# Ad_-_ESP-12F.net
KiCad netlist of a schematic drawn in Altium Designer
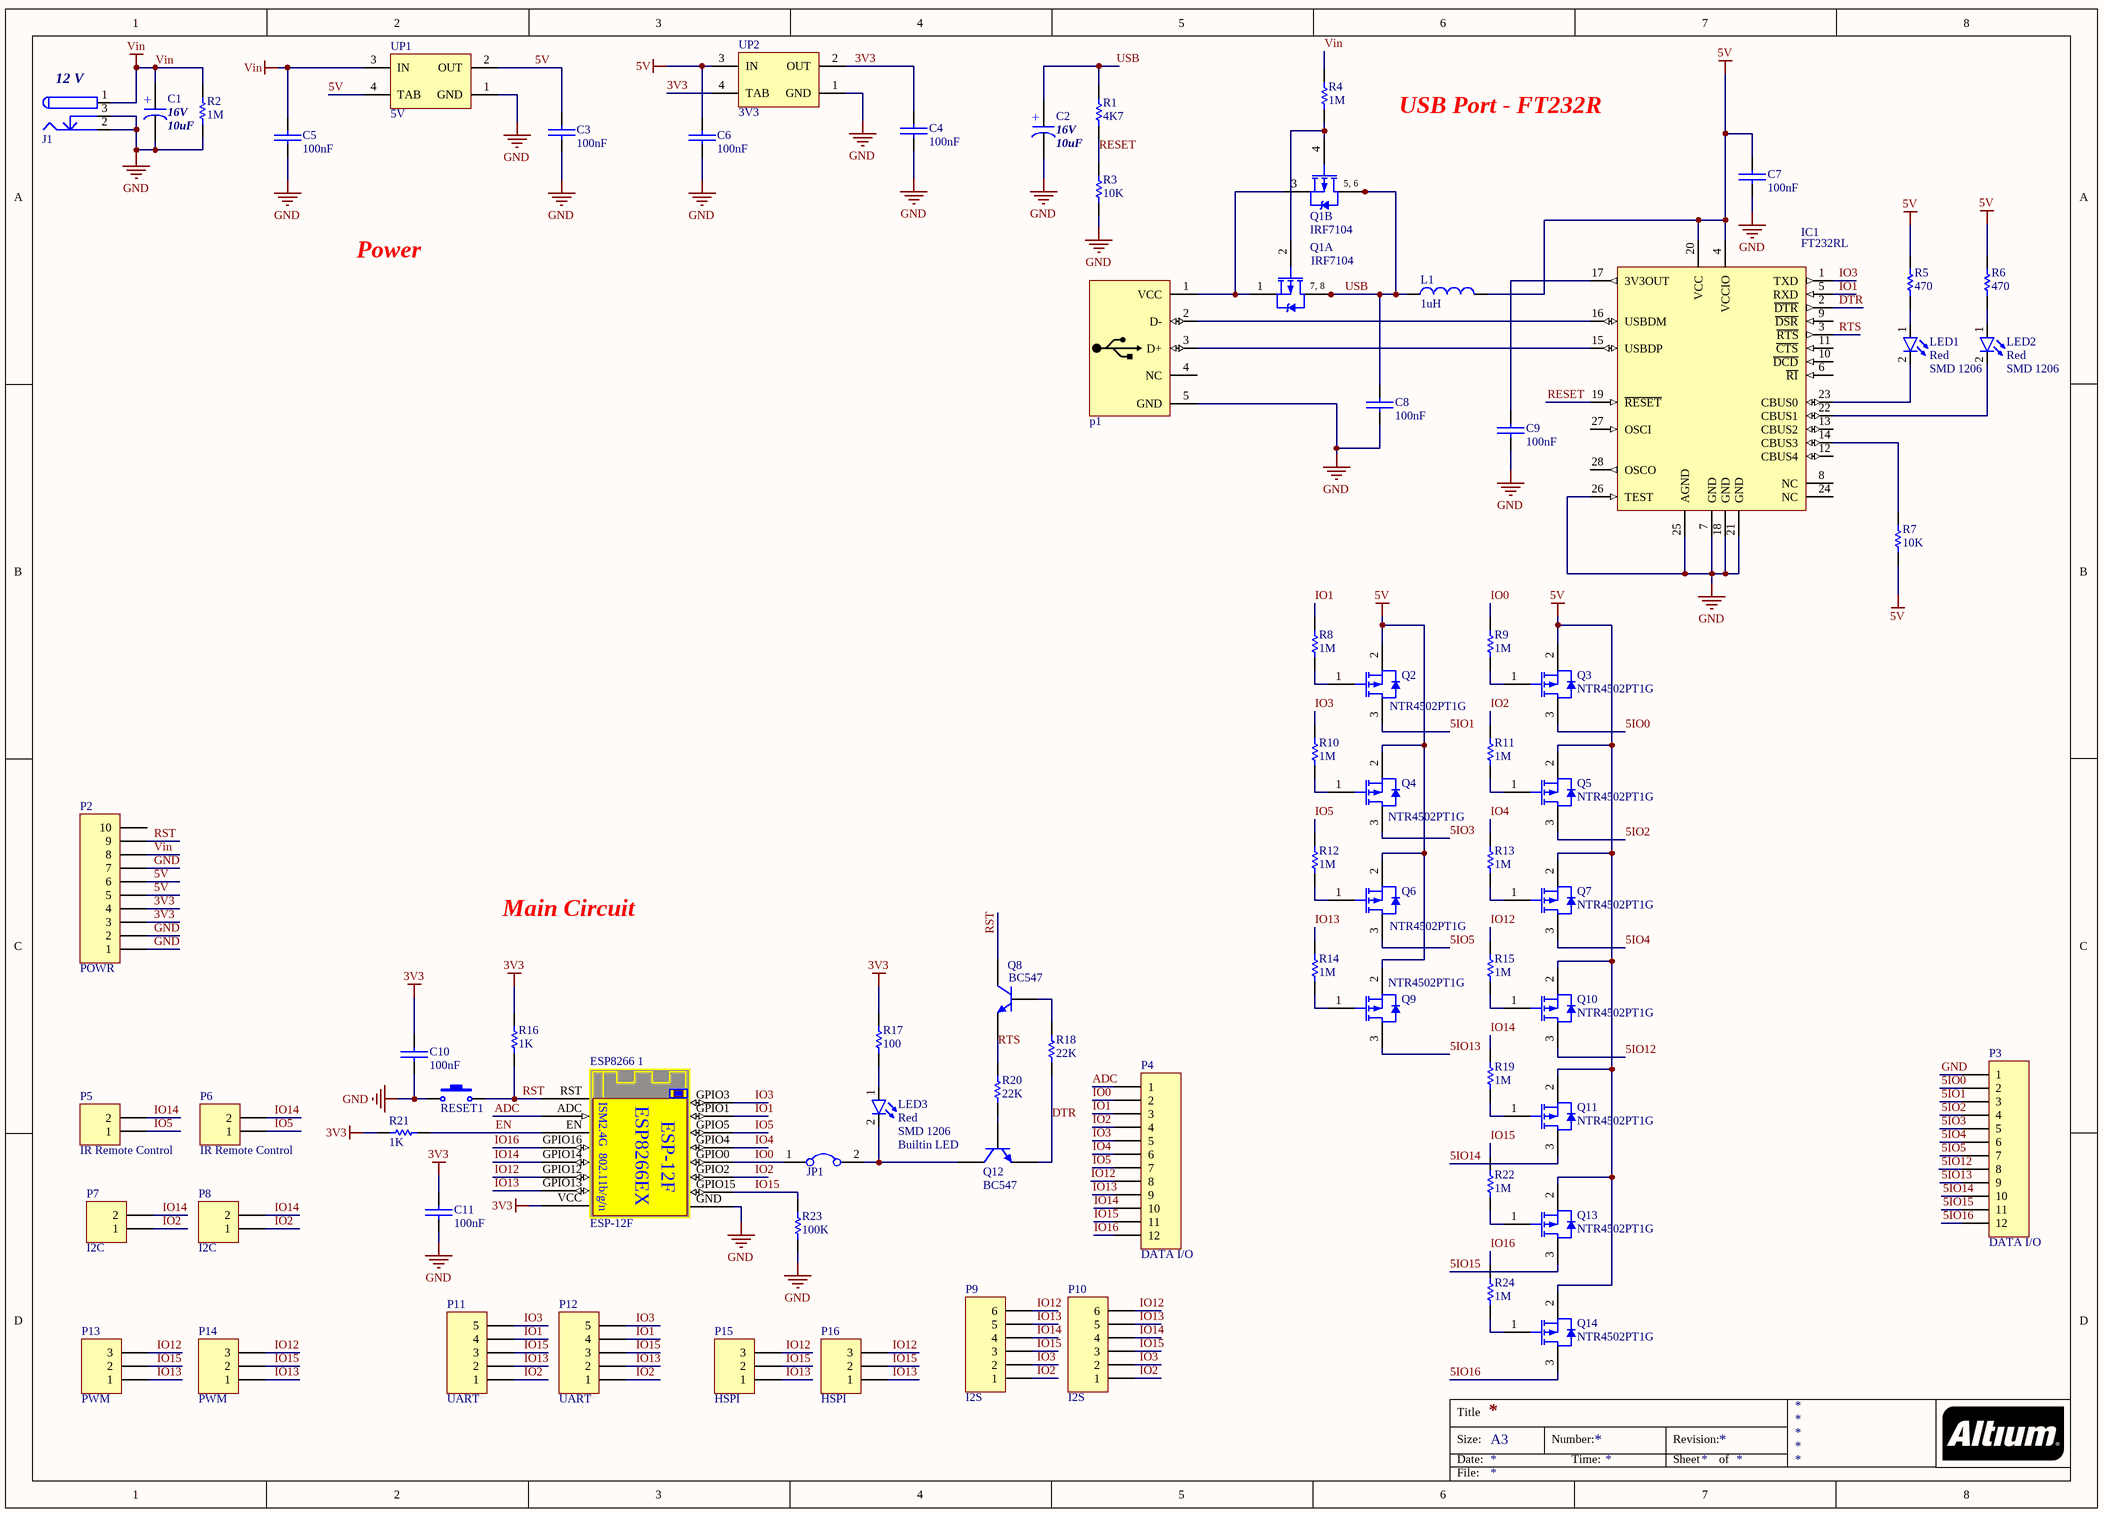
[diagram p0: Ad - ESP-12F.SchDoc]

(export (version "E")
  (design (tool "Eeschema 10.0.6"))
  (components
    (comp (ref "C1")
      (value "10uF")
      (footprint "AECS")
      (description "SMD Capacitors")
      (fields (field (name "VOLTAGE") "16V"))
      (libsource (lib "Ad - ESP-12F") (part "SMD Capacitors"))
    )
    (comp (ref "C2")
      (value "10uF")
      (footprint "AECS")
      (description "SMD Capacitors")
      (fields (field (name "VOLTAGE") "16V"))
      (libsource (lib "Ad - ESP-12F") (part "SMD Capacitors"))
    )
    (comp (ref "C3")
      (value "100nF")
      (footprint "SMD_CAP_1206")
      (description "Bipolar Capacitor")
      (fields (field (name "VOLTAGE") "100V") (field (name "DESIGNER") "Saeid Jorablo"))
      (libsource (lib "My Library") (part "Cap-Bipolar"))
    )
    (comp (ref "C4")
      (value "100nF")
      (footprint "SMD_CAP_1206")
      (description "Bipolar Capacitor")
      (fields (field (name "VOLTAGE") "100V") (field (name "DESIGNER") "Saeid Jorablo"))
      (libsource (lib "My Library") (part "Cap-Bipolar"))
    )
    (comp (ref "C5")
      (value "100nF")
      (footprint "SMD_CAP_1206")
      (description "Bipolar Capacitor")
      (fields (field (name "VOLTAGE") "100V") (field (name "DESIGNER") "Saeid Jorablo"))
      (libsource (lib "My Library") (part "Cap-Bipolar"))
    )
    (comp (ref "C6")
      (value "100nF")
      (footprint "SMD_CAP_1206")
      (description "Bipolar Capacitor")
      (fields (field (name "VOLTAGE") "100V") (field (name "DESIGNER") "Saeid Jorablo"))
      (libsource (lib "My Library") (part "Cap-Bipolar"))
    )
    (comp (ref "C7")
      (value "100nF")
      (footprint "SMD_CAP_1206")
      (description "Bipolar Capacitor")
      (fields (field (name "VOLTAGE") "100V") (field (name "DESIGNER") "Saeid Jorablo"))
      (libsource (lib "My Library") (part "Cap-Bipolar"))
    )
    (comp (ref "C8")
      (value "100nF")
      (footprint "SMD_CAP_1206")
      (description "Bipolar Capacitor")
      (fields (field (name "VOLTAGE") "100V") (field (name "DESIGNER") "Saeid Jorablo"))
      (libsource (lib "My Library") (part "Cap-Bipolar"))
    )
    (comp (ref "C9")
      (value "100nF")
      (footprint "SMD_CAP_1206")
      (description "Bipolar Capacitor")
      (fields (field (name "VOLTAGE") "100V") (field (name "DESIGNER") "Saeid Jorablo"))
      (libsource (lib "My Library") (part "Cap-Bipolar"))
    )
    (comp (ref "C10")
      (value "100nF")
      (footprint "SMD_CAP_1206")
      (description "Bipolar Capacitor")
      (fields (field (name "VOLTAGE") "100V") (field (name "DESIGNER") "Saeid Jorablo"))
      (libsource (lib "My Library") (part "Cap-Bipolar"))
    )
    (comp (ref "C11")
      (value "100nF")
      (footprint "SMD_CAP_1206")
      (description "Bipolar Capacitor")
      (fields (field (name "VOLTAGE") "100V") (field (name "DESIGNER") "Saeid Jorablo"))
      (libsource (lib "My Library") (part "Cap-Bipolar"))
    )
    (comp (ref "ESP8266 1")
      (value "ESP-12F")
      (footprint "ESP-12F")
      (description "ESP-12F WiFi Module")
      (libsource (lib "Ad - ESP-12F") (part "ESP-12F WiFi Module"))
    )
    (comp (ref "IC1")
      (value "FT232RL")
      (footprint "SSOP-28_M")
      (description "USB UART Asynchronous Serial Data Transfer Chip, SSOP-28, Tape and Reel")
      (fields (field (name "PUBLISHER") "Altium Limited"))
      (libsource (lib "My Library") (part "FT232RL"))
    )
    (comp (ref "J1")
      (value "DC Power Jack")
      (footprint "DC Power Jack 1")
      (description "DC Power Jack. Center Pin 2.5mm. Diameter: 5.7mm")
      (fields (field (name "DESIGNER") "Ali Hafizi"))
      (libsource (lib "Altium") (part "DC Power Jack"))
    )
    (comp (ref "JP1")
      (value "Jumper")
      (footprint "Jumper Small - 2.54 - BLUE")
      (libsource (lib "Altium") (part "Jumper"))
    )
    (comp (ref "L1")
      (value "1uH")
      (footprint "IND1206")
      (description "TOTAL INDUCTOR SMD PACK")
      (fields (field (name "DESIGNER") "Abbas Basereh"))
      (libsource (lib "Altium") (part "INDUCTOR SMD PACKAGE"))
    )
    (comp (ref "LED1")
      (value "Red")
      (footprint "LED SMD 1206")
      (description "LED")
      (fields
        (field (name "COLOR") "Red")
        (field (name "SIZE") "SMD 1206")
        (field (name "DESIGNER") "Saeid Jorablo")
      )
      (libsource (lib "My Library") (part "LED"))
    )
    (comp (ref "LED2")
      (value "Red")
      (footprint "LED SMD 1206")
      (description "LED")
      (fields
        (field (name "COLOR") "Red")
        (field (name "SIZE") "SMD 1206")
        (field (name "DESIGNER") "Saeid Jorablo")
      )
      (libsource (lib "My Library") (part "LED"))
    )
    (comp (ref "LED3")
      (value "Red")
      (footprint "LED SMD 1206")
      (description "LED")
      (fields
        (field (name "COLOR") "Red")
        (field (name "SIZE") "SMD 1206")
        (field (name "TYPE") "Builtin LED")
        (field (name "DESIGNER") "Saeid Jorablo")
      )
      (libsource (lib "My Library") (part "LED"))
    )
    (comp (ref "p1")
      (value "USB Connector")
      (footprint "USB_AB_BM_SHS")
      (description "USB Connector MICRO-B Type")
      (fields (field (name "DESIGNER") "ABBAS BASEREH") (field (name "PUBLISHER") "ABBAS BASEREH"))
      (libsource (lib "Altium") (part "USB MICRO"))
    )
    (comp (ref "P2")
      (value "POWR")
      (footprint "HDR1X10")
      (description "Header, 10-Pin")
      (fields (field (name "PUBLISHER") "Altium Limited"))
      (libsource (lib "Altium") (part "Header 10"))
    )
    (comp (ref "P3")
      (value "DATA I/O")
      (footprint "HDR1X12")
      (description "Header, 12-Pin")
      (fields (field (name "PUBLISHER") "Altium Limited"))
      (libsource (lib "Altium") (part "Header 12"))
    )
    (comp (ref "P4")
      (value "DATA I/O")
      (footprint "HDR1X12")
      (description "Header, 12-Pin")
      (fields (field (name "PUBLISHER") "Altium Limited"))
      (libsource (lib "Altium") (part "Header 12"))
    )
    (comp (ref "P5")
      (value "IR Remote Control")
      (footprint "HDR1X2")
      (description "Header, 2-Pin")
      (fields (field (name "PUBLISHER") "Altium Limited"))
      (libsource (lib "Altium") (part "Header 2"))
    )
    (comp (ref "P6")
      (value "IR Remote Control")
      (footprint "HDR1X2")
      (description "Header, 2-Pin")
      (fields (field (name "PUBLISHER") "Altium Limited"))
      (libsource (lib "Altium") (part "Header 2"))
    )
    (comp (ref "P7")
      (value "I2C")
      (footprint "HDR1X2")
      (description "Header, 2-Pin")
      (fields (field (name "PUBLISHER") "Altium Limited"))
      (libsource (lib "Altium") (part "Header 2"))
    )
    (comp (ref "P8")
      (value "I2C")
      (footprint "HDR1X2")
      (description "Header, 2-Pin")
      (fields (field (name "PUBLISHER") "Altium Limited"))
      (libsource (lib "Altium") (part "Header 2"))
    )
    (comp (ref "P9")
      (value "I2S")
      (footprint "HDR1X6")
      (description "Header, 6-Pin")
      (fields (field (name "PUBLISHER") "Altium Limited"))
      (libsource (lib "Altium") (part "Header 6"))
    )
    (comp (ref "P10")
      (value "I2S")
      (footprint "HDR1X6")
      (description "Header, 6-Pin")
      (fields (field (name "PUBLISHER") "Altium Limited"))
      (libsource (lib "Altium") (part "Header 6"))
    )
    (comp (ref "P11")
      (value "UART")
      (footprint "HDR1X5")
      (description "Header, 5-Pin")
      (fields (field (name "PUBLISHER") "Altium Limited"))
      (libsource (lib "Altium") (part "Header 5"))
    )
    (comp (ref "P12")
      (value "UART")
      (footprint "HDR1X5")
      (description "Header, 5-Pin")
      (fields (field (name "PUBLISHER") "Altium Limited"))
      (libsource (lib "Altium") (part "Header 5"))
    )
    (comp (ref "P13")
      (value "PWM")
      (footprint "HDR1X3")
      (description "Header, 3-Pin")
      (fields (field (name "PUBLISHER") "Altium Limited"))
      (libsource (lib "Altium") (part "Header 3"))
    )
    (comp (ref "P14")
      (value "PWM")
      (footprint "HDR1X3")
      (description "Header, 3-Pin")
      (fields (field (name "PUBLISHER") "Altium Limited"))
      (libsource (lib "Altium") (part "Header 3"))
    )
    (comp (ref "P15")
      (value "HSPI")
      (footprint "HDR1X3")
      (description "Header, 3-Pin")
      (fields (field (name "PUBLISHER") "Altium Limited"))
      (libsource (lib "Altium") (part "Header 3"))
    )
    (comp (ref "P16")
      (value "HSPI")
      (footprint "HDR1X3")
      (description "Header, 3-Pin")
      (fields (field (name "PUBLISHER") "Altium Limited"))
      (libsource (lib "Altium") (part "Header 3"))
    )
    (comp (ref "Q1")
      (value "IRF7104")
      (footprint "SO-8_M")
      (description "HEXFET Power MOSFET")
      (fields (field (name "PUBLISHER") "Altium Limited"))
      (libsource (lib "IR Discrete MOSFET - Power") (part "IRF7104"))
    )
    (comp (ref "Q2")
      (value "NTR4502PT1G")
      (footprint "ONSC-SOT-23-3-318-08_V")
      (description "Power MOSFET, -30 V, -1.95 A, Single, P-Channel, 3-Pin SOT-23, Pb-Free, Tape and Reel")
      (fields (field (name "MANUFACTURER") "On Semiconductor"))
      (libsource (lib "ON Semi MOSFETs") (part "NTR4502PT1G"))
    )
    (comp (ref "Q3")
      (value "NTR4502PT1G")
      (footprint "ONSC-SOT-23-3-318-08_V")
      (description "Power MOSFET, -30 V, -1.95 A, Single, P-Channel, 3-Pin SOT-23, Pb-Free, Tape and Reel")
      (fields (field (name "MANUFACTURER") "On Semiconductor"))
      (libsource (lib "ON Semi MOSFETs") (part "NTR4502PT1G"))
    )
    (comp (ref "Q4")
      (value "NTR4502PT1G")
      (footprint "ONSC-SOT-23-3-318-08_V")
      (description "Power MOSFET, -30 V, -1.95 A, Single, P-Channel, 3-Pin SOT-23, Pb-Free, Tape and Reel")
      (fields (field (name "MANUFACTURER") "On Semiconductor"))
      (libsource (lib "ON Semi MOSFETs") (part "NTR4502PT1G"))
    )
    (comp (ref "Q5")
      (value "NTR4502PT1G")
      (footprint "ONSC-SOT-23-3-318-08_V")
      (description "Power MOSFET, -30 V, -1.95 A, Single, P-Channel, 3-Pin SOT-23, Pb-Free, Tape and Reel")
      (fields (field (name "MANUFACTURER") "On Semiconductor"))
      (libsource (lib "ON Semi MOSFETs") (part "NTR4502PT1G"))
    )
    (comp (ref "Q6")
      (value "NTR4502PT1G")
      (footprint "ONSC-SOT-23-3-318-08_V")
      (description "Power MOSFET, -30 V, -1.95 A, Single, P-Channel, 3-Pin SOT-23, Pb-Free, Tape and Reel")
      (fields (field (name "MANUFACTURER") "On Semiconductor"))
      (libsource (lib "ON Semi MOSFETs") (part "NTR4502PT1G"))
    )
    (comp (ref "Q7")
      (value "NTR4502PT1G")
      (footprint "ONSC-SOT-23-3-318-08_V")
      (description "Power MOSFET, -30 V, -1.95 A, Single, P-Channel, 3-Pin SOT-23, Pb-Free, Tape and Reel")
      (fields (field (name "MANUFACTURER") "On Semiconductor"))
      (libsource (lib "ON Semi MOSFETs") (part "NTR4502PT1G"))
    )
    (comp (ref "Q8")
      (value "BC547")
      (footprint "SOT23_M")
      (description "45 V, 500 mA NPN general-purpose transistors")
      (fields (field (name "PUBLISHER") "Abbas Basereh"))
      (libsource (lib "Altium") (part "BC337"))
    )
    (comp (ref "Q9")
      (value "NTR4502PT1G")
      (footprint "ONSC-SOT-23-3-318-08_V")
      (description "Power MOSFET, -30 V, -1.95 A, Single, P-Channel, 3-Pin SOT-23, Pb-Free, Tape and Reel")
      (fields (field (name "MANUFACTURER") "On Semiconductor"))
      (libsource (lib "ON Semi MOSFETs") (part "NTR4502PT1G"))
    )
    (comp (ref "Q10")
      (value "NTR4502PT1G")
      (footprint "ONSC-SOT-23-3-318-08_V")
      (description "Power MOSFET, -30 V, -1.95 A, Single, P-Channel, 3-Pin SOT-23, Pb-Free, Tape and Reel")
      (fields (field (name "MANUFACTURER") "On Semiconductor"))
      (libsource (lib "ON Semi MOSFETs") (part "NTR4502PT1G"))
    )
    (comp (ref "Q11")
      (value "NTR4502PT1G")
      (footprint "ONSC-SOT-23-3-318-08_V")
      (description "Power MOSFET, -30 V, -1.95 A, Single, P-Channel, 3-Pin SOT-23, Pb-Free, Tape and Reel")
      (fields (field (name "MANUFACTURER") "On Semiconductor"))
      (libsource (lib "ON Semi MOSFETs") (part "NTR4502PT1G"))
    )
    (comp (ref "Q12")
      (value "BC547")
      (footprint "SOT23_M")
      (description "45 V, 500 mA NPN general-purpose transistors")
      (fields (field (name "PUBLISHER") "Abbas Basereh"))
      (libsource (lib "Altium") (part "BC337"))
    )
    (comp (ref "Q13")
      (value "NTR4502PT1G")
      (footprint "ONSC-SOT-23-3-318-08_V")
      (description "Power MOSFET, -30 V, -1.95 A, Single, P-Channel, 3-Pin SOT-23, Pb-Free, Tape and Reel")
      (fields (field (name "MANUFACTURER") "On Semiconductor"))
      (libsource (lib "ON Semi MOSFETs") (part "NTR4502PT1G"))
    )
    (comp (ref "Q14")
      (value "NTR4502PT1G")
      (footprint "ONSC-SOT-23-3-318-08_V")
      (description "Power MOSFET, -30 V, -1.95 A, Single, P-Channel, 3-Pin SOT-23, Pb-Free, Tape and Reel")
      (fields (field (name "MANUFACTURER") "On Semiconductor"))
      (libsource (lib "ON Semi MOSFETs") (part "NTR4502PT1G"))
    )
    (comp (ref "R1")
      (value "4K7")
      (footprint "RES1206 _(3216X08L)")
      (description "TOTAL SMD RESISTOR PACK")
      (fields (field (name "DESIGNER") "Abbas Basereh"))
      (libsource (lib "Altium") (part "RES SMD PACKAGE"))
    )
    (comp (ref "R2")
      (value "1M")
      (footprint "RES1206 _(3216X08L)")
      (description "TOTAL SMD RESISTOR PACK")
      (fields (field (name "DESIGNER") "Abbas Basereh"))
      (libsource (lib "Altium") (part "RES SMD PACKAGE"))
    )
    (comp (ref "R3")
      (value "10K")
      (footprint "RES1206 _(3216X08L)")
      (description "TOTAL SMD RESISTOR PACK")
      (fields (field (name "DESIGNER") "Abbas Basereh"))
      (libsource (lib "Altium") (part "RES SMD PACKAGE"))
    )
    (comp (ref "R4")
      (value "1M")
      (footprint "RES1206 _(3216X08L)")
      (description "TOTAL SMD RESISTOR PACK")
      (fields (field (name "DESIGNER") "Abbas Basereh"))
      (libsource (lib "Altium") (part "RES SMD PACKAGE"))
    )
    (comp (ref "R5")
      (value "470")
      (footprint "RES1206 _(3216X08L)")
      (description "TOTAL SMD RESISTOR PACK")
      (fields (field (name "DESIGNER") "Abbas Basereh"))
      (libsource (lib "Altium") (part "RES SMD PACKAGE"))
    )
    (comp (ref "R6")
      (value "470")
      (footprint "RES1206 _(3216X08L)")
      (description "TOTAL SMD RESISTOR PACK")
      (fields (field (name "DESIGNER") "Abbas Basereh"))
      (libsource (lib "Altium") (part "RES SMD PACKAGE"))
    )
    (comp (ref "R7")
      (value "10K")
      (footprint "RES1206 _(3216X08L)")
      (description "TOTAL SMD RESISTOR PACK")
      (fields (field (name "DESIGNER") "Abbas Basereh"))
      (libsource (lib "Altium") (part "RES SMD PACKAGE"))
    )
    (comp (ref "R8")
      (value "1M")
      (footprint "RES1206 _(3216X08L)")
      (description "TOTAL SMD RESISTOR PACK")
      (fields (field (name "DESIGNER") "Abbas Basereh"))
      (libsource (lib "Altium") (part "RES SMD PACKAGE"))
    )
    (comp (ref "R9")
      (value "1M")
      (footprint "RES1206 _(3216X08L)")
      (description "TOTAL SMD RESISTOR PACK")
      (fields (field (name "DESIGNER") "Abbas Basereh"))
      (libsource (lib "Altium") (part "RES SMD PACKAGE"))
    )
    (comp (ref "R10")
      (value "1M")
      (footprint "RES1206 _(3216X08L)")
      (description "TOTAL SMD RESISTOR PACK")
      (fields (field (name "DESIGNER") "Abbas Basereh"))
      (libsource (lib "Altium") (part "RES SMD PACKAGE"))
    )
    (comp (ref "R11")
      (value "1M")
      (footprint "RES1206 _(3216X08L)")
      (description "TOTAL SMD RESISTOR PACK")
      (fields (field (name "DESIGNER") "Abbas Basereh"))
      (libsource (lib "Altium") (part "RES SMD PACKAGE"))
    )
    (comp (ref "R12")
      (value "1M")
      (footprint "RES1206 _(3216X08L)")
      (description "TOTAL SMD RESISTOR PACK")
      (fields (field (name "DESIGNER") "Abbas Basereh"))
      (libsource (lib "Altium") (part "RES SMD PACKAGE"))
    )
    (comp (ref "R13")
      (value "1M")
      (footprint "RES1206 _(3216X08L)")
      (description "TOTAL SMD RESISTOR PACK")
      (fields (field (name "DESIGNER") "Abbas Basereh"))
      (libsource (lib "Altium") (part "RES SMD PACKAGE"))
    )
    (comp (ref "R14")
      (value "1M")
      (footprint "RES1206 _(3216X08L)")
      (description "TOTAL SMD RESISTOR PACK")
      (fields (field (name "DESIGNER") "Abbas Basereh"))
      (libsource (lib "Altium") (part "RES SMD PACKAGE"))
    )
    (comp (ref "R15")
      (value "1M")
      (footprint "RES1206 _(3216X08L)")
      (description "TOTAL SMD RESISTOR PACK")
      (fields (field (name "DESIGNER") "Abbas Basereh"))
      (libsource (lib "Altium") (part "RES SMD PACKAGE"))
    )
    (comp (ref "R16")
      (value "1K")
      (footprint "RES1206 _(3216X08L)")
      (description "TOTAL SMD RESISTOR PACK")
      (fields (field (name "DESIGNER") "Abbas Basereh"))
      (libsource (lib "Altium") (part "RES SMD PACKAGE"))
    )
    (comp (ref "R17")
      (value "100")
      (footprint "RES1206 _(3216X08L)")
      (description "TOTAL SMD RESISTOR PACK")
      (fields (field (name "DESIGNER") "Abbas Basereh"))
      (libsource (lib "Altium") (part "RES SMD PACKAGE"))
    )
    (comp (ref "R18")
      (value "22K")
      (footprint "RES1206 _(3216X08L)")
      (description "TOTAL SMD RESISTOR PACK")
      (fields (field (name "DESIGNER") "Abbas Basereh"))
      (libsource (lib "Altium") (part "RES SMD PACKAGE"))
    )
    (comp (ref "R19")
      (value "1M")
      (footprint "RES1206 _(3216X08L)")
      (description "TOTAL SMD RESISTOR PACK")
      (fields (field (name "DESIGNER") "Abbas Basereh"))
      (libsource (lib "Altium") (part "RES SMD PACKAGE"))
    )
    (comp (ref "R20")
      (value "22K")
      (footprint "RES1206 _(3216X08L)")
      (description "TOTAL SMD RESISTOR PACK")
      (fields (field (name "DESIGNER") "Abbas Basereh"))
      (libsource (lib "Altium") (part "RES SMD PACKAGE"))
    )
    (comp (ref "R21")
      (value "1K")
      (footprint "RES1206 _(3216X08L)")
      (description "TOTAL SMD RESISTOR PACK")
      (fields (field (name "DESIGNER") "Abbas Basereh"))
      (libsource (lib "Altium") (part "RES SMD PACKAGE"))
    )
    (comp (ref "R22")
      (value "1M")
      (footprint "RES1206 _(3216X08L)")
      (description "TOTAL SMD RESISTOR PACK")
      (fields (field (name "DESIGNER") "Abbas Basereh"))
      (libsource (lib "Altium") (part "RES SMD PACKAGE"))
    )
    (comp (ref "R23")
      (value "100K")
      (footprint "RES1206 _(3216X08L)")
      (description "TOTAL SMD RESISTOR PACK")
      (fields (field (name "DESIGNER") "Abbas Basereh"))
      (libsource (lib "Altium") (part "RES SMD PACKAGE"))
    )
    (comp (ref "R24")
      (value "1M")
      (footprint "RES1206 _(3216X08L)")
      (description "TOTAL SMD RESISTOR PACK")
      (fields (field (name "DESIGNER") "Abbas Basereh"))
      (libsource (lib "Altium") (part "RES SMD PACKAGE"))
    )
    (comp (ref "RESET1")
      (value "Switch PB")
      (footprint "SW-PB")
      (description "Push Button Switch")
      (libsource (lib "Altium") (part "Switch PB"))
    )
    (comp (ref "UP1")
      (value "5V")
      (footprint "SOT223_M")
      (description "x.x Volt, 800mA Low-Dropout Linear Regulator, 4-pin SOT-223")
      (fields (field (name "DESIGNER") "Ali Hafizi"))
      (libsource (lib "Altium") (part "AMS1117-x.x"))
    )
    (comp (ref "UP2")
      (value "3V3")
      (footprint "SOT223_M")
      (description "x.x Volt, 800mA Low-Dropout Linear Regulator, 4-pin SOT-223")
      (fields (field (name "DESIGNER") "Ali Hafizi"))
      (libsource (lib "Altium") (part "AMS1117-x.x"))
    )
  )
  (nets
    (net (code "1") (name "/5IO0") (class "Default")
      (node (ref "P3") (pin "2") (pinfunction "2_2") (pintype "passive"))
      (node (ref "Q3") (pin "3") (pinfunction "D_3") (pintype "passive"))
    )
    (net (code "2") (name "/5IO1") (class "Default")
      (node (ref "P3") (pin "3") (pinfunction "3_3") (pintype "passive"))
      (node (ref "Q2") (pin "3") (pinfunction "D_3") (pintype "passive"))
    )
    (net (code "3") (name "/5IO2") (class "Default")
      (node (ref "P3") (pin "4") (pinfunction "4_4") (pintype "passive"))
      (node (ref "Q5") (pin "3") (pinfunction "D_3") (pintype "passive"))
    )
    (net (code "4") (name "/5IO3") (class "Default")
      (node (ref "P3") (pin "5") (pinfunction "5_5") (pintype "passive"))
      (node (ref "Q4") (pin "3") (pinfunction "D_3") (pintype "passive"))
    )
    (net (code "5") (name "/5IO4") (class "Default")
      (node (ref "P3") (pin "6") (pinfunction "6_6") (pintype "passive"))
      (node (ref "Q7") (pin "3") (pinfunction "D_3") (pintype "passive"))
    )
    (net (code "6") (name "/5IO5") (class "Default")
      (node (ref "P3") (pin "7") (pinfunction "7_7") (pintype "passive"))
      (node (ref "Q6") (pin "3") (pinfunction "D_3") (pintype "passive"))
    )
    (net (code "7") (name "/5IO12") (class "Default")
      (node (ref "P3") (pin "8") (pinfunction "8_8") (pintype "passive"))
      (node (ref "Q10") (pin "3") (pinfunction "D_3") (pintype "passive"))
    )
    (net (code "8") (name "/5IO13") (class "Default")
      (node (ref "P3") (pin "9") (pinfunction "9_9") (pintype "passive"))
      (node (ref "Q9") (pin "3") (pinfunction "D_3") (pintype "passive"))
    )
    (net (code "9") (name "/5IO14") (class "Default")
      (node (ref "P3") (pin "10") (pinfunction "10_10") (pintype "passive"))
      (node (ref "Q11") (pin "3") (pinfunction "D_3") (pintype "passive"))
    )
    (net (code "10") (name "/5IO15") (class "Default")
      (node (ref "P3") (pin "11") (pinfunction "11_11") (pintype "passive"))
      (node (ref "Q13") (pin "3") (pinfunction "D_3") (pintype "passive"))
    )
    (net (code "11") (name "/5IO16") (class "Default")
      (node (ref "P3") (pin "12") (pinfunction "12_12") (pintype "passive"))
      (node (ref "Q14") (pin "3") (pinfunction "D_3") (pintype "passive"))
    )
    (net (code "12") (name "/ADC") (class "Default")
      (node (ref "ESP8266 1") (pin "ADC") (pinfunction "A/D_Conversion_result.Input_voltage_range_0-1v,scope:0-1024_ADC") (pintype "input"))
      (node (ref "P4") (pin "1") (pinfunction "1_1") (pintype "passive"))
    )
    (net (code "13") (name "/DTR") (class "Default")
      (node (ref "IC1") (pin "2") (pinfunction "~{DTR}_2") (pintype "output"))
      (node (ref "Q12") (pin "2") (pinfunction "E_2") (pintype "passive"))
      (node (ref "R18") (pin "1") (pinfunction "1_1") (pintype "passive"))
    )
    (net (code "14") (name "/EN") (class "Default")
      (node (ref "ESP8266 1") (pin "EN") (pinfunction "Chip_enable_pin._Active_high_EN") (pintype "power_in"))
      (node (ref "R21") (pin "1") (pinfunction "1_1") (pintype "passive"))
    )
    (net (code "15") (name "/IO0") (class "Default")
      (node (ref "ESP8266 1") (pin "GPIO0") (pinfunction "SPI_CS2_GPIO0") (pintype "bidirectional"))
      (node (ref "JP1") (pin "1") (pinfunction "1_1") (pintype "passive"))
      (node (ref "P4") (pin "2") (pinfunction "2_2") (pintype "passive"))
      (node (ref "R9") (pin "2") (pinfunction "2_2") (pintype "passive"))
    )
    (net (code "16") (name "/IO1") (class "Default")
      (node (ref "ESP8266 1") (pin "GPIO1") (pinfunction "UART_TX_during_?ash_programming;_SPI_CS1_GPIO1") (pintype "bidirectional"))
      (node (ref "IC1") (pin "5") (pinfunction "RXD_5") (pintype "input"))
      (node (ref "P11") (pin "4") (pinfunction "4_4") (pintype "passive"))
      (node (ref "P12") (pin "4") (pinfunction "4_4") (pintype "passive"))
      (node (ref "P4") (pin "3") (pinfunction "3_3") (pintype "passive"))
      (node (ref "R8") (pin "1") (pinfunction "1_1") (pintype "passive"))
    )
    (net (code "17") (name "/IO2") (class "Default")
      (node (ref "ESP8266 1") (pin "GPIO2") (pinfunction "UART_TX_during_?ash_programming_GPIO2") (pintype "bidirectional"))
      (node (ref "P10") (pin "1") (pinfunction "1_1") (pintype "passive"))
      (node (ref "P11") (pin "1") (pinfunction "1_1") (pintype "passive"))
      (node (ref "P12") (pin "1") (pinfunction "1_1") (pintype "passive"))
      (node (ref "P4") (pin "4") (pinfunction "4_4") (pintype "passive"))
      (node (ref "P7") (pin "1") (pinfunction "1_1") (pintype "passive"))
      (node (ref "P8") (pin "1") (pinfunction "1_1") (pintype "passive"))
      (node (ref "P9") (pin "1") (pinfunction "1_1") (pintype "passive"))
      (node (ref "R11") (pin "1") (pinfunction "1_1") (pintype "passive"))
    )
    (net (code "18") (name "/IO3") (class "Default")
      (node (ref "ESP8266 1") (pin "GPIO3") (pinfunction "UART_Rx_during_?ash_programming_GPIO3") (pintype "bidirectional"))
      (node (ref "IC1") (pin "1") (pinfunction "TXD_1") (pintype "output"))
      (node (ref "P10") (pin "2") (pinfunction "2_2") (pintype "passive"))
      (node (ref "P11") (pin "5") (pinfunction "5_5") (pintype "passive"))
      (node (ref "P12") (pin "5") (pinfunction "5_5") (pintype "passive"))
      (node (ref "P4") (pin "5") (pinfunction "5_5") (pintype "passive"))
      (node (ref "P9") (pin "2") (pinfunction "2_2") (pintype "passive"))
      (node (ref "R10") (pin "1") (pinfunction "1_1") (pintype "passive"))
    )
    (net (code "19") (name "/IO4") (class "Default")
      (node (ref "ESP8266 1") (pin "GPIO4") (pinfunction "GPIO4_GPIO4") (pintype "bidirectional"))
      (node (ref "P4") (pin "6") (pinfunction "6_6") (pintype "passive"))
      (node (ref "R13") (pin "1") (pinfunction "1_1") (pintype "passive"))
    )
    (net (code "20") (name "/IO5") (class "Default")
      (node (ref "ESP8266 1") (pin "GPIO5") (pinfunction "GPIO5_GPIO5") (pintype "bidirectional"))
      (node (ref "P4") (pin "7") (pinfunction "7_7") (pintype "passive"))
      (node (ref "P5") (pin "1") (pinfunction "1_1") (pintype "passive"))
      (node (ref "P6") (pin "1") (pinfunction "1_1") (pintype "passive"))
      (node (ref "R12") (pin "1") (pinfunction "1_1") (pintype "passive"))
    )
    (net (code "21") (name "/IO12") (class "Default")
      (node (ref "ESP8266 1") (pin "GPIO12") (pinfunction "HSPI_MISO_GPIO12") (pintype "bidirectional"))
      (node (ref "P10") (pin "6") (pinfunction "6_6") (pintype "passive"))
      (node (ref "P13") (pin "3") (pinfunction "3_3") (pintype "passive"))
      (node (ref "P14") (pin "3") (pinfunction "3_3") (pintype "passive"))
      (node (ref "P15") (pin "3") (pinfunction "3_3") (pintype "passive"))
      (node (ref "P16") (pin "3") (pinfunction "3_3") (pintype "passive"))
      (node (ref "P4") (pin "8") (pinfunction "8_8") (pintype "passive"))
      (node (ref "P9") (pin "6") (pinfunction "6_6") (pintype "passive"))
      (node (ref "R15") (pin "1") (pinfunction "1_1") (pintype "passive"))
    )
    (net (code "22") (name "/IO13") (class "Default")
      (node (ref "ESP8266 1") (pin "GPIO13") (pinfunction "HSPI_MOSI;_UART0_CTS_GPIO13") (pintype "bidirectional"))
      (node (ref "P10") (pin "5") (pinfunction "5_5") (pintype "passive"))
      (node (ref "P11") (pin "2") (pinfunction "2_2") (pintype "passive"))
      (node (ref "P12") (pin "2") (pinfunction "2_2") (pintype "passive"))
      (node (ref "P13") (pin "1") (pinfunction "1_1") (pintype "passive"))
      (node (ref "P14") (pin "1") (pinfunction "1_1") (pintype "passive"))
      (node (ref "P15") (pin "1") (pinfunction "1_1") (pintype "passive"))
      (node (ref "P16") (pin "1") (pinfunction "1_1") (pintype "passive"))
      (node (ref "P4") (pin "9") (pinfunction "9_9") (pintype "passive"))
      (node (ref "P9") (pin "5") (pinfunction "5_5") (pintype "passive"))
      (node (ref "R14") (pin "1") (pinfunction "1_1") (pintype "passive"))
    )
    (net (code "23") (name "/IO14") (class "Default")
      (node (ref "ESP8266 1") (pin "GPIO14") (pinfunction "HSPI_CLK_GPIO14") (pintype "bidirectional"))
      (node (ref "P10") (pin "4") (pinfunction "4_4") (pintype "passive"))
      (node (ref "P4") (pin "10") (pinfunction "10_10") (pintype "passive"))
      (node (ref "P5") (pin "2") (pinfunction "2_2") (pintype "passive"))
      (node (ref "P6") (pin "2") (pinfunction "2_2") (pintype "passive"))
      (node (ref "P7") (pin "2") (pinfunction "2_2") (pintype "passive"))
      (node (ref "P8") (pin "2") (pinfunction "2_2") (pintype "passive"))
      (node (ref "P9") (pin "4") (pinfunction "4_4") (pintype "passive"))
      (node (ref "R19") (pin "1") (pinfunction "1_1") (pintype "passive"))
    )
    (net (code "24") (name "/IO15") (class "Default")
      (node (ref "ESP8266 1") (pin "GPIO15") (pinfunction "HSPI_CS;_UART0_RTS_GPIO15") (pintype "bidirectional"))
      (node (ref "P10") (pin "3") (pinfunction "3_3") (pintype "passive"))
      (node (ref "P11") (pin "3") (pinfunction "3_3") (pintype "passive"))
      (node (ref "P12") (pin "3") (pinfunction "3_3") (pintype "passive"))
      (node (ref "P13") (pin "2") (pinfunction "2_2") (pintype "passive"))
      (node (ref "P14") (pin "2") (pinfunction "2_2") (pintype "passive"))
      (node (ref "P15") (pin "2") (pinfunction "2_2") (pintype "passive"))
      (node (ref "P16") (pin "2") (pinfunction "2_2") (pintype "passive"))
      (node (ref "P4") (pin "11") (pinfunction "11_11") (pintype "passive"))
      (node (ref "P9") (pin "3") (pinfunction "3_3") (pintype "passive"))
      (node (ref "R22") (pin "1") (pinfunction "1_1") (pintype "passive"))
      (node (ref "R23") (pin "2") (pinfunction "2_2") (pintype "passive"))
    )
    (net (code "25") (name "/IO16") (class "Default")
      (node (ref "ESP8266 1") (pin "GPIO16") (pinfunction "XPD_DCDC_-_Deep-sleep_wakeup_(need_to_be_connected_to_EXT_RSTB)_GPIO16") (pintype "bidirectional"))
      (node (ref "P4") (pin "12") (pinfunction "12_12") (pintype "passive"))
      (node (ref "R24") (pin "1") (pinfunction "1_1") (pintype "passive"))
    )
    (net (code "26") (name "/RESET") (class "Default")
      (node (ref "IC1") (pin "19") (pinfunction "~{RESET}_19") (pintype "input"))
      (node (ref "R1") (pin "1") (pinfunction "1_1") (pintype "passive"))
      (node (ref "R3") (pin "2") (pinfunction "2_2") (pintype "passive"))
    )
    (net (code "27") (name "/RST") (class "Default")
      (node (ref "ESP8266 1") (pin "RST") (pinfunction "External_reset_signal_(Low_voltage_level:_active)_RST") (pintype "power_in"))
      (node (ref "P2") (pin "9") (pinfunction "9_9") (pintype "passive"))
      (node (ref "Q8") (pin "3") (pinfunction "C_3") (pintype "passive"))
      (node (ref "R16") (pin "1") (pinfunction "1_1") (pintype "passive"))
      (node (ref "RESET1") (pin "2") (pinfunction "2_2") (pintype "passive"))
    )
    (net (code "28") (name "/RTS") (class "Default")
      (node (ref "IC1") (pin "3") (pinfunction "~{RTS}_3") (pintype "output"))
      (node (ref "Q8") (pin "2") (pinfunction "E_2") (pintype "passive"))
      (node (ref "R20") (pin "2") (pinfunction "2_2") (pintype "passive"))
    )
    (net (code "29") (name "/USB") (class "Default")
      (node (ref "C2") (pin "1") (pinfunction "1_1") (pintype "passive"))
      (node (ref "C8") (pin "2") (pinfunction "-_2") (pintype "passive"))
      (node (ref "L1") (pin "1") (pinfunction "1_1") (pintype "passive"))
      (node (ref "Q1") (pin "5") (pinfunction "D_5") (pintype "passive"))
      (node (ref "Q1") (pin "6") (pinfunction "D_6") (pintype "passive"))
      (node (ref "Q1") (pin "7") (pinfunction "D_7") (pintype "passive"))
      (node (ref "Q1") (pin "8") (pinfunction "D_8") (pintype "passive"))
      (node (ref "R1") (pin "2") (pinfunction "2_2") (pintype "passive"))
    )
    (net (code "30") (name "3V3") (class "Default")
      (node (ref "C10") (pin "1") (pinfunction "+_1") (pintype "passive"))
      (node (ref "C11") (pin "1") (pinfunction "+_1") (pintype "passive"))
      (node (ref "C4") (pin "1") (pinfunction "+_1") (pintype "passive"))
      (node (ref "ESP8266 1") (pin "VCC") (pinfunction "Analog_Power_2.5V_~_3.6V_VCC") (pintype "power_in"))
      (node (ref "P2") (pin "3") (pinfunction "3_3") (pintype "passive"))
      (node (ref "P2") (pin "4") (pinfunction "4_4") (pintype "passive"))
      (node (ref "R16") (pin "2") (pinfunction "2_2") (pintype "passive"))
      (node (ref "R17") (pin "2") (pinfunction "2_2") (pintype "passive"))
      (node (ref "R21") (pin "2") (pinfunction "2_2") (pintype "passive"))
      (node (ref "UP2") (pin "2") (pinfunction "OUT_2") (pintype "power_in"))
      (node (ref "UP2") (pin "4") (pinfunction "TAB_4") (pintype "power_in"))
    )
    (net (code "31") (name "5V") (class "Default")
      (node (ref "C3") (pin "1") (pinfunction "+_1") (pintype "passive"))
      (node (ref "C6") (pin "2") (pinfunction "-_2") (pintype "passive"))
      (node (ref "C7") (pin "1") (pinfunction "+_1") (pintype "passive"))
      (node (ref "IC1") (pin "20") (pinfunction "VCC_20") (pintype "power_in"))
      (node (ref "IC1") (pin "4") (pinfunction "VCCIO_4") (pintype "power_in"))
      (node (ref "L1") (pin "2") (pinfunction "2_2") (pintype "passive"))
      (node (ref "P2") (pin "5") (pinfunction "5_5") (pintype "passive"))
      (node (ref "P2") (pin "6") (pinfunction "6_6") (pintype "passive"))
      (node (ref "Q10") (pin "2") (pinfunction "S_2") (pintype "passive"))
      (node (ref "Q11") (pin "2") (pinfunction "S_2") (pintype "passive"))
      (node (ref "Q13") (pin "2") (pinfunction "S_2") (pintype "passive"))
      (node (ref "Q14") (pin "2") (pinfunction "S_2") (pintype "passive"))
      (node (ref "Q2") (pin "2") (pinfunction "S_2") (pintype "passive"))
      (node (ref "Q3") (pin "2") (pinfunction "S_2") (pintype "passive"))
      (node (ref "Q4") (pin "2") (pinfunction "S_2") (pintype "passive"))
      (node (ref "Q5") (pin "2") (pinfunction "S_2") (pintype "passive"))
      (node (ref "Q6") (pin "2") (pinfunction "S_2") (pintype "passive"))
      (node (ref "Q7") (pin "2") (pinfunction "S_2") (pintype "passive"))
      (node (ref "Q9") (pin "2") (pinfunction "S_2") (pintype "passive"))
      (node (ref "R5") (pin "2") (pinfunction "2_2") (pintype "passive"))
      (node (ref "R6") (pin "2") (pinfunction "2_2") (pintype "passive"))
      (node (ref "R7") (pin "1") (pinfunction "1_1") (pintype "passive"))
      (node (ref "UP1") (pin "2") (pinfunction "OUT_2") (pintype "power_in"))
      (node (ref "UP1") (pin "4") (pinfunction "TAB_4") (pintype "power_in"))
      (node (ref "UP2") (pin "3") (pinfunction "IN_3") (pintype "power_in"))
    )
    (net (code "32") (name "GND") (class "Default")
      (node (ref "C1") (pin "2") (pinfunction "2_2") (pintype "passive"))
      (node (ref "C10") (pin "2") (pinfunction "-_2") (pintype "passive"))
      (node (ref "C11") (pin "2") (pinfunction "-_2") (pintype "passive"))
      (node (ref "C2") (pin "2") (pinfunction "2_2") (pintype "passive"))
      (node (ref "C3") (pin "2") (pinfunction "-_2") (pintype "passive"))
      (node (ref "C4") (pin "2") (pinfunction "-_2") (pintype "passive"))
      (node (ref "C5") (pin "1") (pinfunction "+_1") (pintype "passive"))
      (node (ref "C6") (pin "1") (pinfunction "+_1") (pintype "passive"))
      (node (ref "C7") (pin "2") (pinfunction "-_2") (pintype "passive"))
      (node (ref "C8") (pin "1") (pinfunction "+_1") (pintype "passive"))
      (node (ref "C9") (pin "1") (pinfunction "+_1") (pintype "passive"))
      (node (ref "ESP8266 1") (pin "GND") (pinfunction "GND_GND") (pintype "power_in"))
      (node (ref "IC1") (pin "18") (pinfunction "GND_18") (pintype "power_in"))
      (node (ref "IC1") (pin "21") (pinfunction "GND_21") (pintype "power_in"))
      (node (ref "IC1") (pin "25") (pinfunction "AGND_25") (pintype "power_in"))
      (node (ref "IC1") (pin "26") (pinfunction "TEST_26") (pintype "input"))
      (node (ref "IC1") (pin "7") (pinfunction "GND_7") (pintype "power_in"))
      (node (ref "J1") (pin "2") (pinfunction "2_2") (pintype "power_in"))
      (node (ref "J1") (pin "3") (pinfunction "3_3") (pintype "power_in"))
      (node (ref "P2") (pin "1") (pinfunction "1_1") (pintype "passive"))
      (node (ref "P2") (pin "2") (pinfunction "2_2") (pintype "passive"))
      (node (ref "P2") (pin "7") (pinfunction "7_7") (pintype "passive"))
      (node (ref "P3") (pin "1") (pinfunction "1_1") (pintype "passive"))
      (node (ref "R2") (pin "1") (pinfunction "1_1") (pintype "passive"))
      (node (ref "R23") (pin "1") (pinfunction "1_1") (pintype "passive"))
      (node (ref "R3") (pin "1") (pinfunction "1_1") (pintype "passive"))
      (node (ref "RESET1") (pin "1") (pinfunction "1_1") (pintype "passive"))
      (node (ref "UP1") (pin "1") (pinfunction "GND_1") (pintype "power_in"))
      (node (ref "UP2") (pin "1") (pinfunction "GND_1") (pintype "power_in"))
      (node (ref "p1") (pin "5") (pinfunction "GND_5") (pintype "power_in"))
    )
    (net (code "33") (name "Net-(C9--)") (class "Default")
      (node (ref "C9") (pin "2") (pinfunction "-_2") (pintype "passive"))
      (node (ref "IC1") (pin "17") (pinfunction "3V3OUT_17") (pintype "output"))
    )
    (net (code "34") (name "Net-(IC1-CBUS0)") (class "Default")
      (node (ref "IC1") (pin "23") (pinfunction "CBUS0_23") (pintype "bidirectional"))
      (node (ref "LED1") (pin "2") (pinfunction "K_2") (pintype "passive"))
    )
    (net (code "35") (name "Net-(IC1-CBUS1)") (class "Default")
      (node (ref "IC1") (pin "22") (pinfunction "CBUS1_22") (pintype "bidirectional"))
      (node (ref "LED2") (pin "2") (pinfunction "K_2") (pintype "passive"))
    )
    (net (code "36") (name "Net-(IC1-CBUS3)") (class "Default")
      (node (ref "IC1") (pin "14") (pinfunction "CBUS3_14") (pintype "bidirectional"))
      (node (ref "R7") (pin "2") (pinfunction "2_2") (pintype "passive"))
    )
    (net (code "37") (name "Net-(IC1-USBDM)") (class "Default")
      (node (ref "IC1") (pin "16") (pinfunction "USBDM_16") (pintype "bidirectional"))
      (node (ref "p1") (pin "2") (pinfunction "D-_2") (pintype "bidirectional"))
    )
    (net (code "38") (name "Net-(IC1-USBDP)") (class "Default")
      (node (ref "IC1") (pin "15") (pinfunction "USBDP_15") (pintype "bidirectional"))
      (node (ref "p1") (pin "3") (pinfunction "D+_3") (pintype "bidirectional"))
    )
    (net (code "39") (name "Net-(LED1-A)") (class "Default")
      (node (ref "LED1") (pin "1") (pinfunction "A_1") (pintype "passive"))
      (node (ref "R5") (pin "1") (pinfunction "1_1") (pintype "passive"))
    )
    (net (code "40") (name "Net-(LED2-A)") (class "Default")
      (node (ref "LED2") (pin "1") (pinfunction "A_1") (pintype "passive"))
      (node (ref "R6") (pin "1") (pinfunction "1_1") (pintype "passive"))
    )
    (net (code "41") (name "Net-(LED3-A)") (class "Default")
      (node (ref "LED3") (pin "1") (pinfunction "A_1") (pintype "passive"))
      (node (ref "R17") (pin "1") (pinfunction "1_1") (pintype "passive"))
    )
    (net (code "42") (name "Net-(LED3-K)") (class "Default")
      (node (ref "JP1") (pin "2") (pinfunction "2_2") (pintype "passive"))
      (node (ref "LED3") (pin "2") (pinfunction "K_2") (pintype "passive"))
      (node (ref "Q12") (pin "3") (pinfunction "C_3") (pintype "passive"))
    )
    (net (code "43") (name "Net-(Q1A-G)") (class "Default")
      (node (ref "Q1") (pin "2") (pinfunction "G_2") (pintype "passive"))
      (node (ref "Q1") (pin "4") (pinfunction "G_4") (pintype "passive"))
      (node (ref "R4") (pin "1") (pinfunction "1_1") (pintype "passive"))
    )
    (net (code "44") (name "Net-(Q1A-S)") (class "Default")
      (node (ref "Q1") (pin "1") (pinfunction "S_1") (pintype "passive"))
      (node (ref "Q1") (pin "3") (pinfunction "S_3") (pintype "passive"))
      (node (ref "p1") (pin "1") (pinfunction "VCC_1") (pintype "power_in"))
    )
    (net (code "45") (name "Net-(Q2-G)") (class "Default")
      (node (ref "Q2") (pin "1") (pinfunction "G_1") (pintype "passive"))
      (node (ref "R8") (pin "2") (pinfunction "2_2") (pintype "passive"))
    )
    (net (code "46") (name "Net-(Q3-G)") (class "Default")
      (node (ref "Q3") (pin "1") (pinfunction "G_1") (pintype "passive"))
      (node (ref "R9") (pin "1") (pinfunction "1_1") (pintype "passive"))
    )
    (net (code "47") (name "Net-(Q4-G)") (class "Default")
      (node (ref "Q4") (pin "1") (pinfunction "G_1") (pintype "passive"))
      (node (ref "R10") (pin "2") (pinfunction "2_2") (pintype "passive"))
    )
    (net (code "48") (name "Net-(Q5-G)") (class "Default")
      (node (ref "Q5") (pin "1") (pinfunction "G_1") (pintype "passive"))
      (node (ref "R11") (pin "2") (pinfunction "2_2") (pintype "passive"))
    )
    (net (code "49") (name "Net-(Q6-G)") (class "Default")
      (node (ref "Q6") (pin "1") (pinfunction "G_1") (pintype "passive"))
      (node (ref "R12") (pin "2") (pinfunction "2_2") (pintype "passive"))
    )
    (net (code "50") (name "Net-(Q7-G)") (class "Default")
      (node (ref "Q7") (pin "1") (pinfunction "G_1") (pintype "passive"))
      (node (ref "R13") (pin "2") (pinfunction "2_2") (pintype "passive"))
    )
    (net (code "51") (name "Net-(Q8-B)") (class "Default")
      (node (ref "Q8") (pin "1") (pinfunction "B_1") (pintype "passive"))
      (node (ref "R18") (pin "2") (pinfunction "2_2") (pintype "passive"))
    )
    (net (code "52") (name "Net-(Q9-G)") (class "Default")
      (node (ref "Q9") (pin "1") (pinfunction "G_1") (pintype "passive"))
      (node (ref "R14") (pin "2") (pinfunction "2_2") (pintype "passive"))
    )
    (net (code "53") (name "Net-(Q10-G)") (class "Default")
      (node (ref "Q10") (pin "1") (pinfunction "G_1") (pintype "passive"))
      (node (ref "R15") (pin "2") (pinfunction "2_2") (pintype "passive"))
    )
    (net (code "54") (name "Net-(Q11-G)") (class "Default")
      (node (ref "Q11") (pin "1") (pinfunction "G_1") (pintype "passive"))
      (node (ref "R19") (pin "2") (pinfunction "2_2") (pintype "passive"))
    )
    (net (code "55") (name "Net-(Q12-B)") (class "Default")
      (node (ref "Q12") (pin "1") (pinfunction "B_1") (pintype "passive"))
      (node (ref "R20") (pin "1") (pinfunction "1_1") (pintype "passive"))
    )
    (net (code "56") (name "Net-(Q13-G)") (class "Default")
      (node (ref "Q13") (pin "1") (pinfunction "G_1") (pintype "passive"))
      (node (ref "R22") (pin "2") (pinfunction "2_2") (pintype "passive"))
    )
    (net (code "57") (name "Net-(Q14-G)") (class "Default")
      (node (ref "Q14") (pin "1") (pinfunction "G_1") (pintype "passive"))
      (node (ref "R24") (pin "2") (pinfunction "2_2") (pintype "passive"))
    )
    (net (code "58") (name "Vin") (class "Default")
      (node (ref "C1") (pin "1") (pinfunction "1_1") (pintype "passive"))
      (node (ref "C5") (pin "2") (pinfunction "-_2") (pintype "passive"))
      (node (ref "J1") (pin "1") (pinfunction "1_1") (pintype "power_in"))
      (node (ref "P2") (pin "8") (pinfunction "8_8") (pintype "passive"))
      (node (ref "R2") (pin "2") (pinfunction "2_2") (pintype "passive"))
      (node (ref "R4") (pin "2") (pinfunction "2_2") (pintype "passive"))
      (node (ref "UP1") (pin "3") (pinfunction "IN_3") (pintype "power_in"))
    )
    (net (code "59") (name "unconnected-(IC1-CBUS2-Pad13)") (class "Default")
      (node (ref "IC1") (pin "13") (pinfunction "CBUS2_13") (pintype "bidirectional"))
    )
    (net (code "60") (name "unconnected-(IC1-CBUS4-Pad12)") (class "Default")
      (node (ref "IC1") (pin "12") (pinfunction "CBUS4_12") (pintype "bidirectional"))
    )
    (net (code "61") (name "unconnected-(IC1-NC-Pad8)") (class "Default")
      (node (ref "IC1") (pin "8") (pinfunction "NC_8") (pintype "passive"))
    )
    (net (code "62") (name "unconnected-(IC1-NC-Pad24)") (class "Default")
      (node (ref "IC1") (pin "24") (pinfunction "NC_24") (pintype "passive"))
    )
    (net (code "63") (name "unconnected-(IC1-OSCI-Pad27)") (class "Default")
      (node (ref "IC1") (pin "27") (pinfunction "OSCI_27") (pintype "input"))
    )
    (net (code "64") (name "unconnected-(IC1-OSCO-Pad28)") (class "Default")
      (node (ref "IC1") (pin "28") (pinfunction "OSCO_28") (pintype "output"))
    )
    (net (code "65") (name "unconnected-(IC1-~{CTS}-Pad11)") (class "Default")
      (node (ref "IC1") (pin "11") (pinfunction "~{CTS}_11") (pintype "input"))
    )
    (net (code "66") (name "unconnected-(IC1-~{DCD}-Pad10)") (class "Default")
      (node (ref "IC1") (pin "10") (pinfunction "~{DCD}_10") (pintype "input"))
    )
    (net (code "67") (name "unconnected-(IC1-~{DSR}-Pad9)") (class "Default")
      (node (ref "IC1") (pin "9") (pinfunction "~{DSR}_9") (pintype "input"))
    )
    (net (code "68") (name "unconnected-(IC1-~{RI}-Pad6)") (class "Default")
      (node (ref "IC1") (pin "6") (pinfunction "~{RI}_6") (pintype "input"))
    )
    (net (code "69") (name "unconnected-(P2-Pad10)") (class "Default")
      (node (ref "P2") (pin "10") (pinfunction "10_10") (pintype "passive"))
    )
    (net (code "70") (name "unconnected-(p1-NC-Pad4)") (class "Default")
      (node (ref "p1") (pin "4") (pinfunction "NC_4") (pintype "passive"))
    )
  )
)
